# MACH_VXL.net
KiCad netlist of a schematic drawn in Altium Designer
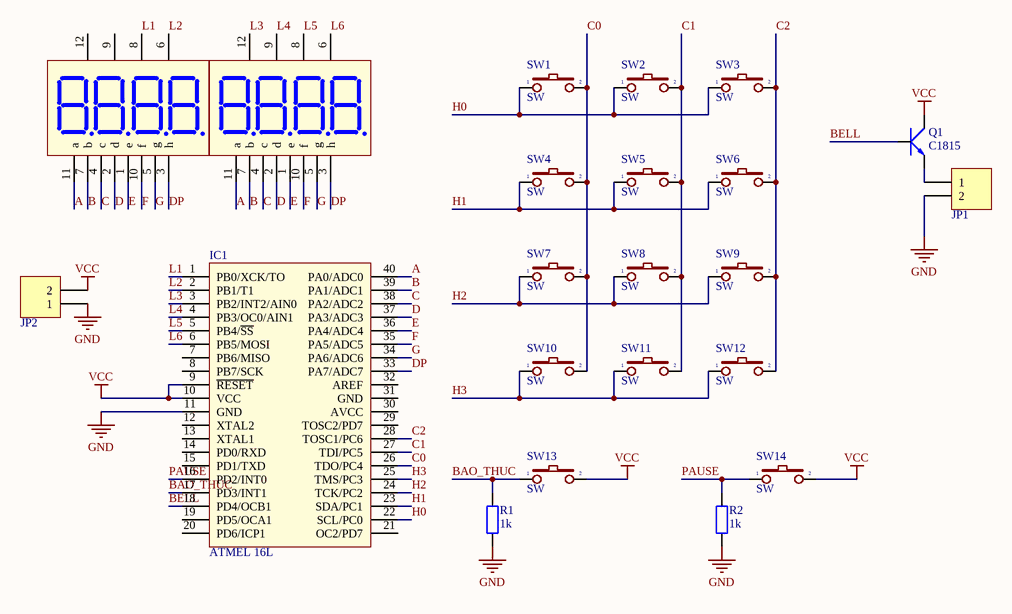
[diagram p0: MACH_VXL.SchDoc]

(export (version "E")
  (design (tool "Eeschema 10.0.6"))
  (components
    (comp (ref "D1")
      (value "~")
      (footprint "LED7SEG-4-0.36")
      (description "4 digit 7 segment anot")
      (libsource (lib "BYTECH_HW_LIB_2019 (1)") (part "LED7SEG-A-0.36-4DIGIT"))
    )
    (comp (ref "D2")
      (value "~")
      (footprint "LED7SEG-4-0.36")
      (description "4 digit 7 segment anot")
      (libsource (lib "BYTECH_HW_LIB_2019 (1)") (part "LED7SEG-A-0.36-4DIGIT"))
    )
    (comp (ref "IC1")
      (value "ATMEL 16L")
      (footprint "DIP40/W0.6")
      (description "8-Bit AVR Microcontroller with 16K Bytes of In-System Programmable Flash Memory")
      (libsource (lib "syhaunguyen") (part "Atmega16L"))
    )
    (comp (ref "JP1")
      (value "Header 2_1")
      (footprint "HED2")
      (description "Header, 2-Pin")
      (fields (field (name "MANUFACTURER") "Generic Components"))
      (libsource (lib "syhaunguyen") (part "Header 2_1"))
    )
    (comp (ref "JP2")
      (value "Header 2_1")
      (footprint "HED2")
      (description "Header, 2-Pin")
      (fields (field (name "MANUFACTURER") "Generic Components"))
      (libsource (lib "") (part "Header 2_1_1"))
    )
    (comp (ref "Q1")
      (value "C1815")
      (footprint "QTO-92")
      (description "NPN 600mW, ECB")
      (libsource (lib "syhaunguyen") (part "C1815"))
    )
    (comp (ref "R1")
      (value "1k")
      (footprint "R1/4W")
      (description "Resistor 1/4W")
      (libsource (lib "syhaunguyen") (part "R1/4W"))
    )
    (comp (ref "R2")
      (value "1k")
      (footprint "R1/4W")
      (description "Resistor 1/4W")
      (libsource (lib "syhaunguyen") (part "R1/4W"))
    )
    (comp (ref "SW1")
      (value "SW")
      (footprint "SW2")
      (description "Switch button 2 pin")
      (libsource (lib "syhaunguyen") (part "SW2"))
    )
    (comp (ref "SW2")
      (value "SW")
      (footprint "SW2")
      (description "Switch button 2 pin")
      (libsource (lib "syhaunguyen") (part "SW2"))
    )
    (comp (ref "SW3")
      (value "SW")
      (footprint "SW2")
      (description "Switch button 2 pin")
      (libsource (lib "syhaunguyen") (part "SW2"))
    )
    (comp (ref "SW4")
      (value "SW")
      (footprint "SW2")
      (description "Switch button 2 pin")
      (libsource (lib "syhaunguyen") (part "SW2"))
    )
    (comp (ref "SW5")
      (value "SW")
      (footprint "SW2")
      (description "Switch button 2 pin")
      (libsource (lib "syhaunguyen") (part "SW2"))
    )
    (comp (ref "SW6")
      (value "SW")
      (footprint "SW2")
      (description "Switch button 2 pin")
      (libsource (lib "syhaunguyen") (part "SW2"))
    )
    (comp (ref "SW7")
      (value "SW")
      (footprint "SW2")
      (description "Switch button 2 pin")
      (libsource (lib "syhaunguyen") (part "SW2"))
    )
    (comp (ref "SW8")
      (value "SW")
      (footprint "SW2")
      (description "Switch button 2 pin")
      (libsource (lib "syhaunguyen") (part "SW2"))
    )
    (comp (ref "SW9")
      (value "SW")
      (footprint "SW2")
      (description "Switch button 2 pin")
      (libsource (lib "syhaunguyen") (part "SW2"))
    )
    (comp (ref "SW10")
      (value "SW")
      (footprint "SW2")
      (description "Switch button 2 pin")
      (libsource (lib "syhaunguyen") (part "SW2"))
    )
    (comp (ref "SW11")
      (value "SW")
      (footprint "SW2")
      (description "Switch button 2 pin")
      (libsource (lib "syhaunguyen") (part "SW2"))
    )
    (comp (ref "SW12")
      (value "SW")
      (footprint "SW2")
      (description "Switch button 2 pin")
      (libsource (lib "syhaunguyen") (part "SW2"))
    )
    (comp (ref "SW13")
      (value "SW")
      (footprint "SW2")
      (description "Switch button 2 pin")
      (libsource (lib "syhaunguyen") (part "SW2"))
    )
    (comp (ref "SW14")
      (value "SW")
      (footprint "SW2")
      (description "Switch button 2 pin")
      (libsource (lib "syhaunguyen") (part "SW2"))
    )
  )
  (nets
    (net (code "1") (name "/A") (class "Default")
      (node (ref "D1") (pin "11") (pinfunction "a_11") (pintype "passive"))
      (node (ref "D2") (pin "11") (pinfunction "a_11") (pintype "passive"))
      (node (ref "IC1") (pin "40") (pinfunction "PA0/ADC0_40") (pintype "passive"))
    )
    (net (code "2") (name "/B") (class "Default")
      (node (ref "D1") (pin "7") (pinfunction "b_7") (pintype "passive"))
      (node (ref "D2") (pin "7") (pinfunction "b_7") (pintype "passive"))
      (node (ref "IC1") (pin "39") (pinfunction "PA1/ADC1_39") (pintype "passive"))
    )
    (net (code "3") (name "/BAO_THUC") (class "Default")
      (node (ref "IC1") (pin "17") (pinfunction "PD3/INT1_17") (pintype "passive"))
      (node (ref "R1") (pin "2") (pinfunction "2_2") (pintype "passive"))
      (node (ref "SW13") (pin "1") (pinfunction "1_1") (pintype "passive"))
    )
    (net (code "4") (name "/BELL") (class "Default")
      (node (ref "IC1") (pin "18") (pinfunction "PD4/OCB1_18") (pintype "passive"))
      (node (ref "Q1") (pin "3") (pinfunction "B_3") (pintype "passive"))
    )
    (net (code "5") (name "/C") (class "Default")
      (node (ref "D1") (pin "4") (pinfunction "c_4") (pintype "passive"))
      (node (ref "D2") (pin "4") (pinfunction "c_4") (pintype "passive"))
      (node (ref "IC1") (pin "38") (pinfunction "PA2/ADC2_38") (pintype "passive"))
    )
    (net (code "6") (name "/C0") (class "Default")
      (node (ref "IC1") (pin "26") (pinfunction "TDO/PC4_26") (pintype "passive"))
      (node (ref "SW1") (pin "2") (pinfunction "2_2") (pintype "passive"))
      (node (ref "SW10") (pin "2") (pinfunction "2_2") (pintype "passive"))
      (node (ref "SW4") (pin "2") (pinfunction "2_2") (pintype "passive"))
      (node (ref "SW7") (pin "2") (pinfunction "2_2") (pintype "passive"))
    )
    (net (code "7") (name "/C1") (class "Default")
      (node (ref "IC1") (pin "27") (pinfunction "TDI/PC5_27") (pintype "passive"))
      (node (ref "SW11") (pin "2") (pinfunction "2_2") (pintype "passive"))
      (node (ref "SW2") (pin "2") (pinfunction "2_2") (pintype "passive"))
      (node (ref "SW5") (pin "2") (pinfunction "2_2") (pintype "passive"))
      (node (ref "SW8") (pin "2") (pinfunction "2_2") (pintype "passive"))
    )
    (net (code "8") (name "/C2") (class "Default")
      (node (ref "IC1") (pin "28") (pinfunction "TOSC1/PC6_28") (pintype "passive"))
      (node (ref "SW12") (pin "2") (pinfunction "2_2") (pintype "passive"))
      (node (ref "SW3") (pin "2") (pinfunction "2_2") (pintype "passive"))
      (node (ref "SW6") (pin "2") (pinfunction "2_2") (pintype "passive"))
      (node (ref "SW9") (pin "2") (pinfunction "2_2") (pintype "passive"))
    )
    (net (code "9") (name "/D") (class "Default")
      (node (ref "D1") (pin "2") (pinfunction "d_2") (pintype "passive"))
      (node (ref "D2") (pin "2") (pinfunction "d_2") (pintype "passive"))
      (node (ref "IC1") (pin "37") (pinfunction "PA3/ADC3_37") (pintype "passive"))
    )
    (net (code "10") (name "/DP") (class "Default")
      (node (ref "D1") (pin "3") (pinfunction "h_3") (pintype "passive"))
      (node (ref "D2") (pin "3") (pinfunction "h_3") (pintype "passive"))
      (node (ref "IC1") (pin "33") (pinfunction "PA7/ADC7_33") (pintype "passive"))
    )
    (net (code "11") (name "/E") (class "Default")
      (node (ref "D1") (pin "1") (pinfunction "e_1") (pintype "passive"))
      (node (ref "D2") (pin "1") (pinfunction "e_1") (pintype "passive"))
      (node (ref "IC1") (pin "36") (pinfunction "PA4/ADC4_36") (pintype "passive"))
    )
    (net (code "12") (name "/F") (class "Default")
      (node (ref "D1") (pin "10") (pinfunction "f_10") (pintype "passive"))
      (node (ref "D2") (pin "10") (pinfunction "f_10") (pintype "passive"))
      (node (ref "IC1") (pin "35") (pinfunction "PA5/ADC5_35") (pintype "passive"))
    )
    (net (code "13") (name "/G") (class "Default")
      (node (ref "D1") (pin "5") (pinfunction "g_5") (pintype "passive"))
      (node (ref "D2") (pin "5") (pinfunction "g_5") (pintype "passive"))
      (node (ref "IC1") (pin "34") (pinfunction "PA6/ADC6_34") (pintype "passive"))
    )
    (net (code "14") (name "/H0") (class "Default")
      (node (ref "IC1") (pin "22") (pinfunction "SCL/PC0_22") (pintype "passive"))
      (node (ref "SW1") (pin "1") (pinfunction "1_1") (pintype "passive"))
      (node (ref "SW2") (pin "1") (pinfunction "1_1") (pintype "passive"))
      (node (ref "SW3") (pin "1") (pinfunction "1_1") (pintype "passive"))
    )
    (net (code "15") (name "/H1") (class "Default")
      (node (ref "IC1") (pin "23") (pinfunction "SDA/PC1_23") (pintype "passive"))
      (node (ref "SW4") (pin "1") (pinfunction "1_1") (pintype "passive"))
      (node (ref "SW5") (pin "1") (pinfunction "1_1") (pintype "passive"))
      (node (ref "SW6") (pin "1") (pinfunction "1_1") (pintype "passive"))
    )
    (net (code "16") (name "/H2") (class "Default")
      (node (ref "IC1") (pin "24") (pinfunction "TCK/PC2_24") (pintype "passive"))
      (node (ref "SW7") (pin "1") (pinfunction "1_1") (pintype "passive"))
      (node (ref "SW8") (pin "1") (pinfunction "1_1") (pintype "passive"))
      (node (ref "SW9") (pin "1") (pinfunction "1_1") (pintype "passive"))
    )
    (net (code "17") (name "/H3") (class "Default")
      (node (ref "IC1") (pin "25") (pinfunction "TMS/PC3_25") (pintype "passive"))
      (node (ref "SW10") (pin "1") (pinfunction "1_1") (pintype "passive"))
      (node (ref "SW11") (pin "1") (pinfunction "1_1") (pintype "passive"))
      (node (ref "SW12") (pin "1") (pinfunction "1_1") (pintype "passive"))
    )
    (net (code "18") (name "/L1") (class "Default")
      (node (ref "D1") (pin "8") (pinfunction "V3_8") (pintype "passive"))
      (node (ref "IC1") (pin "1") (pinfunction "PB0/XCK/TO_1") (pintype "passive"))
    )
    (net (code "19") (name "/L2") (class "Default")
      (node (ref "D1") (pin "6") (pinfunction "V4_6") (pintype "passive"))
      (node (ref "IC1") (pin "2") (pinfunction "PB1/T1_2") (pintype "passive"))
    )
    (net (code "20") (name "/L3") (class "Default")
      (node (ref "D2") (pin "12") (pinfunction "V1_12") (pintype "passive"))
      (node (ref "IC1") (pin "3") (pinfunction "PB2/INT2/AIN0_3") (pintype "passive"))
    )
    (net (code "21") (name "/L4") (class "Default")
      (node (ref "D2") (pin "9") (pinfunction "V2_9") (pintype "passive"))
      (node (ref "IC1") (pin "4") (pinfunction "PB3/OC0/AIN1_4") (pintype "passive"))
    )
    (net (code "22") (name "/L5") (class "Default")
      (node (ref "D2") (pin "8") (pinfunction "V3_8") (pintype "passive"))
      (node (ref "IC1") (pin "5") (pinfunction "PB4/~{SS}_5") (pintype "passive"))
    )
    (net (code "23") (name "/L6") (class "Default")
      (node (ref "D2") (pin "6") (pinfunction "V4_6") (pintype "passive"))
      (node (ref "IC1") (pin "6") (pinfunction "PB5/MOSI_6") (pintype "passive"))
    )
    (net (code "24") (name "/PAUSE") (class "Default")
      (node (ref "IC1") (pin "16") (pinfunction "PD2/INT0_16") (pintype "passive"))
      (node (ref "R2") (pin "2") (pinfunction "2_2") (pintype "passive"))
      (node (ref "SW14") (pin "1") (pinfunction "1_1") (pintype "passive"))
    )
    (net (code "25") (name "GND") (class "Default")
      (node (ref "IC1") (pin "11") (pinfunction "GND_11") (pintype "passive"))
      (node (ref "JP1") (pin "2") (pinfunction "2_2") (pintype "passive"))
      (node (ref "JP2") (pin "1") (pinfunction "1_1") (pintype "passive"))
      (node (ref "R1") (pin "1") (pinfunction "1_1") (pintype "passive"))
      (node (ref "R2") (pin "1") (pinfunction "1_1") (pintype "passive"))
    )
    (net (code "26") (name "Net-(Q1-E)") (class "Default")
      (node (ref "JP1") (pin "1") (pinfunction "1_1") (pintype "passive"))
      (node (ref "Q1") (pin "1") (pinfunction "E_1") (pintype "passive"))
    )
    (net (code "27") (name "VCC") (class "Default")
      (node (ref "IC1") (pin "10") (pinfunction "VCC_10") (pintype "passive"))
      (node (ref "IC1") (pin "9") (pinfunction "~{RESET}_9") (pintype "passive"))
      (node (ref "JP2") (pin "2") (pinfunction "2_2") (pintype "passive"))
      (node (ref "Q1") (pin "2") (pinfunction "C_2") (pintype "passive"))
      (node (ref "SW13") (pin "2") (pinfunction "2_2") (pintype "passive"))
      (node (ref "SW14") (pin "2") (pinfunction "2_2") (pintype "passive"))
    )
    (net (code "28") (name "unconnected-(D1-V1-Pad12)") (class "Default")
      (node (ref "D1") (pin "12") (pinfunction "V1_12") (pintype "passive"))
    )
    (net (code "29") (name "unconnected-(D1-V2-Pad9)") (class "Default")
      (node (ref "D1") (pin "9") (pinfunction "V2_9") (pintype "passive"))
    )
    (net (code "30") (name "unconnected-(IC1-AREF-Pad32)") (class "Default")
      (node (ref "IC1") (pin "32") (pinfunction "AREF_32") (pintype "passive"))
    )
    (net (code "31") (name "unconnected-(IC1-AVCC-Pad30)") (class "Default")
      (node (ref "IC1") (pin "30") (pinfunction "AVCC_30") (pintype "passive"))
    )
    (net (code "32") (name "unconnected-(IC1-GND-Pad31)") (class "Default")
      (node (ref "IC1") (pin "31") (pinfunction "GND_31") (pintype "passive"))
    )
    (net (code "33") (name "unconnected-(IC1-OC2{slash}PD7-Pad21)") (class "Default")
      (node (ref "IC1") (pin "21") (pinfunction "OC2/PD7_21") (pintype "passive"))
    )
    (net (code "34") (name "unconnected-(IC1-PB6{slash}MISO-Pad7)") (class "Default")
      (node (ref "IC1") (pin "7") (pinfunction "PB6/MISO_7") (pintype "passive"))
    )
    (net (code "35") (name "unconnected-(IC1-PB7{slash}SCK-Pad8)") (class "Default")
      (node (ref "IC1") (pin "8") (pinfunction "PB7/SCK_8") (pintype "passive"))
    )
    (net (code "36") (name "unconnected-(IC1-PD0{slash}RXD-Pad14)") (class "Default")
      (node (ref "IC1") (pin "14") (pinfunction "PD0/RXD_14") (pintype "passive"))
    )
    (net (code "37") (name "unconnected-(IC1-PD1{slash}TXD-Pad15)") (class "Default")
      (node (ref "IC1") (pin "15") (pinfunction "PD1/TXD_15") (pintype "passive"))
    )
    (net (code "38") (name "unconnected-(IC1-PD5{slash}OCA1-Pad19)") (class "Default")
      (node (ref "IC1") (pin "19") (pinfunction "PD5/OCA1_19") (pintype "passive"))
    )
    (net (code "39") (name "unconnected-(IC1-PD6{slash}ICP1-Pad20)") (class "Default")
      (node (ref "IC1") (pin "20") (pinfunction "PD6/ICP1_20") (pintype "passive"))
    )
    (net (code "40") (name "unconnected-(IC1-TOSC2{slash}PD7-Pad29)") (class "Default")
      (node (ref "IC1") (pin "29") (pinfunction "TOSC2/PD7_29") (pintype "passive"))
    )
    (net (code "41") (name "unconnected-(IC1-XTAL1-Pad13)") (class "Default")
      (node (ref "IC1") (pin "13") (pinfunction "XTAL1_13") (pintype "passive"))
    )
    (net (code "42") (name "unconnected-(IC1-XTAL2-Pad12)") (class "Default")
      (node (ref "IC1") (pin "12") (pinfunction "XTAL2_12") (pintype "passive"))
    )
  )
)
